# NavigationBoard.net
KiCad netlist of a schematic drawn in EAGLE
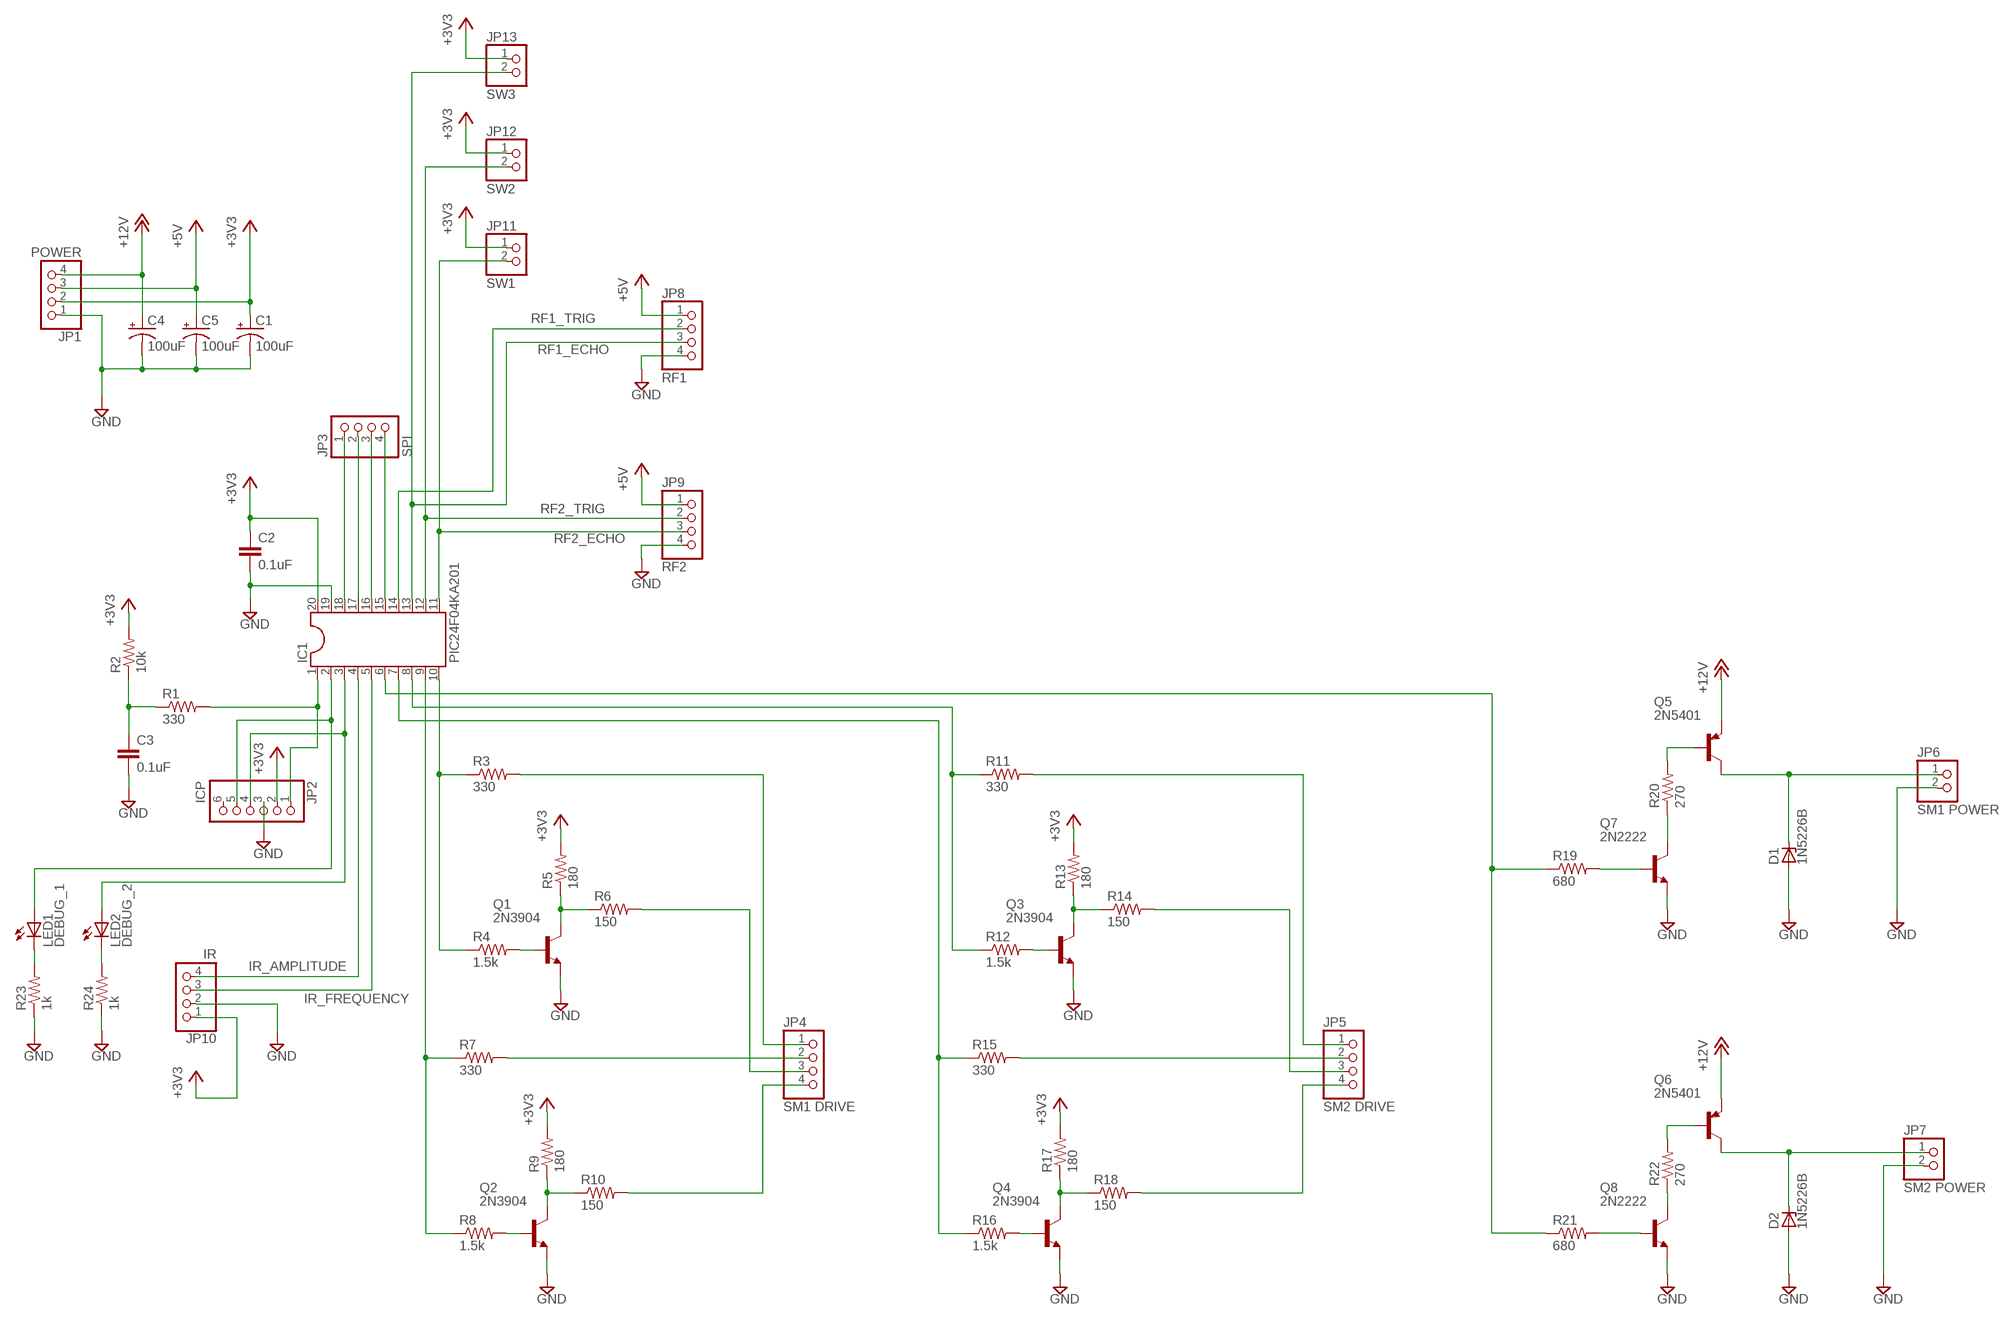
[diagram p0: schematic, sheet 1]

(export (version "E")
  (design (tool "Eeschema 10.0.6"))
  (components
    (comp (ref "C1")
      (value "100uF")
      (footprint "eagle-import:E2,5-7")
      (libsource (lib "eagle-import") (part "CPOL-USE2.5-7"))
    )
    (comp (ref "C2")
      (value "0.1uF")
      (footprint "eagle-import:C0805")
      (libsource (lib "eagle-import") (part "C-EUC0805"))
    )
    (comp (ref "C3")
      (value "0.1uF")
      (footprint "eagle-import:C0805")
      (libsource (lib "eagle-import") (part "C-EUC0805"))
    )
    (comp (ref "C4")
      (value "100uF")
      (footprint "eagle-import:E2,5-7")
      (libsource (lib "eagle-import") (part "CPOL-USE2.5-7"))
    )
    (comp (ref "C5")
      (value "100uF")
      (footprint "eagle-import:E2,5-7")
      (libsource (lib "eagle-import") (part "CPOL-USE2.5-7"))
    )
    (comp (ref "D1")
      (value "1N5226B")
      (footprint "eagle-import:DO35Z10")
      (libsource (lib "eagle-import") (part "ZPD"))
    )
    (comp (ref "D2")
      (value "1N5226B")
      (footprint "eagle-import:DO35Z10")
      (libsource (lib "eagle-import") (part "ZPD"))
    )
    (comp (ref "IC1")
      (value "PIC24F04KA201")
      (footprint "eagle-import:SOCKET-20")
      (libsource (lib "eagle-import") (part "DIL20S"))
    )
    (comp (ref "JP1")
      (value "POWER")
      (footprint "eagle-import:1X04")
      (libsource (lib "eagle-import") (part "PINHD-1X4"))
    )
    (comp (ref "JP2")
      (value "ICP")
      (footprint "eagle-import:1X06")
      (libsource (lib "eagle-import") (part "PINHD-1X6"))
    )
    (comp (ref "JP3")
      (value "SPI")
      (footprint "eagle-import:1X04")
      (libsource (lib "eagle-import") (part "PINHD-1X4"))
    )
    (comp (ref "JP4")
      (value "SM1 DRIVE")
      (footprint "eagle-import:1X04")
      (libsource (lib "eagle-import") (part "PINHD-1X4"))
    )
    (comp (ref "JP5")
      (value "SM2 DRIVE")
      (footprint "eagle-import:1X04")
      (libsource (lib "eagle-import") (part "PINHD-1X4"))
    )
    (comp (ref "JP6")
      (value "SM1 POWER")
      (footprint "eagle-import:1X02")
      (libsource (lib "eagle-import") (part "PINHD-1X2"))
    )
    (comp (ref "JP7")
      (value "SM2 POWER")
      (footprint "eagle-import:1X02")
      (libsource (lib "eagle-import") (part "PINHD-1X2"))
    )
    (comp (ref "JP8")
      (value "RF1")
      (footprint "eagle-import:1X04")
      (libsource (lib "eagle-import") (part "PINHD-1X4"))
    )
    (comp (ref "JP9")
      (value "RF2")
      (footprint "eagle-import:1X04")
      (libsource (lib "eagle-import") (part "PINHD-1X4"))
    )
    (comp (ref "JP10")
      (value "IR")
      (footprint "eagle-import:1X04")
      (libsource (lib "eagle-import") (part "PINHD-1X4"))
    )
    (comp (ref "JP11")
      (value "SW1")
      (footprint "eagle-import:1X02")
      (libsource (lib "eagle-import") (part "PINHD-1X2"))
    )
    (comp (ref "JP12")
      (value "SW2")
      (footprint "eagle-import:1X02")
      (libsource (lib "eagle-import") (part "PINHD-1X2"))
    )
    (comp (ref "JP13")
      (value "SW3")
      (footprint "eagle-import:1X02")
      (libsource (lib "eagle-import") (part "PINHD-1X2"))
    )
    (comp (ref "LED1")
      (value "DEBUG_1")
      (footprint "eagle-import:LED3MM")
      (libsource (lib "eagle-import") (part "LED3MM"))
    )
    (comp (ref "LED2")
      (value "DEBUG_2")
      (footprint "eagle-import:LED3MM")
      (libsource (lib "eagle-import") (part "LED3MM"))
    )
    (comp (ref "Q1")
      (value "2N3904")
      (footprint "eagle-import:TO92")
      (libsource (lib "eagle-import") (part "2N3904"))
    )
    (comp (ref "Q2")
      (value "2N3904")
      (footprint "eagle-import:TO92")
      (libsource (lib "eagle-import") (part "2N3904"))
    )
    (comp (ref "Q3")
      (value "2N3904")
      (footprint "eagle-import:TO92")
      (libsource (lib "eagle-import") (part "2N3904"))
    )
    (comp (ref "Q4")
      (value "2N3904")
      (footprint "eagle-import:TO92")
      (libsource (lib "eagle-import") (part "2N3904"))
    )
    (comp (ref "Q5")
      (value "2N5401")
      (footprint "eagle-import:TO92")
      (libsource (lib "eagle-import") (part "2N3906"))
    )
    (comp (ref "Q6")
      (value "2N5401")
      (footprint "eagle-import:TO92")
      (libsource (lib "eagle-import") (part "2N3906"))
    )
    (comp (ref "Q7")
      (value "2N2222")
      (footprint "eagle-import:TO92")
      (libsource (lib "eagle-import") (part "2N3904"))
    )
    (comp (ref "Q8")
      (value "2N2222")
      (footprint "eagle-import:TO92")
      (libsource (lib "eagle-import") (part "2N3904"))
    )
    (comp (ref "R1")
      (value "330")
      (footprint "eagle-import:R0805")
      (libsource (lib "eagle-import") (part "R-US_R0805"))
    )
    (comp (ref "R2")
      (value "10k")
      (footprint "eagle-import:R0805")
      (libsource (lib "eagle-import") (part "R-US_R0805"))
    )
    (comp (ref "R3")
      (value "330")
      (footprint "eagle-import:R0805")
      (libsource (lib "eagle-import") (part "R-US_R0805"))
    )
    (comp (ref "R4")
      (value "1.5k")
      (footprint "eagle-import:R0805")
      (libsource (lib "eagle-import") (part "R-US_R0805"))
    )
    (comp (ref "R5")
      (value "180")
      (footprint "eagle-import:R0805")
      (libsource (lib "eagle-import") (part "R-US_R0805"))
    )
    (comp (ref "R6")
      (value "150")
      (footprint "eagle-import:R0805")
      (libsource (lib "eagle-import") (part "R-US_R0805"))
    )
    (comp (ref "R7")
      (value "330")
      (footprint "eagle-import:R0805")
      (libsource (lib "eagle-import") (part "R-US_R0805"))
    )
    (comp (ref "R8")
      (value "1.5k")
      (footprint "eagle-import:R0805")
      (libsource (lib "eagle-import") (part "R-US_R0805"))
    )
    (comp (ref "R9")
      (value "180")
      (footprint "eagle-import:R0805")
      (libsource (lib "eagle-import") (part "R-US_R0805"))
    )
    (comp (ref "R10")
      (value "150")
      (footprint "eagle-import:R0805")
      (libsource (lib "eagle-import") (part "R-US_R0805"))
    )
    (comp (ref "R11")
      (value "330")
      (footprint "eagle-import:R0805")
      (libsource (lib "eagle-import") (part "R-US_R0805"))
    )
    (comp (ref "R12")
      (value "1.5k")
      (footprint "eagle-import:R0805")
      (libsource (lib "eagle-import") (part "R-US_R0805"))
    )
    (comp (ref "R13")
      (value "180")
      (footprint "eagle-import:R0805")
      (libsource (lib "eagle-import") (part "R-US_R0805"))
    )
    (comp (ref "R14")
      (value "150")
      (footprint "eagle-import:R0805")
      (libsource (lib "eagle-import") (part "R-US_R0805"))
    )
    (comp (ref "R15")
      (value "330")
      (footprint "eagle-import:R0805")
      (libsource (lib "eagle-import") (part "R-US_R0805"))
    )
    (comp (ref "R16")
      (value "1.5k")
      (footprint "eagle-import:R0805")
      (libsource (lib "eagle-import") (part "R-US_R0805"))
    )
    (comp (ref "R17")
      (value "180")
      (footprint "eagle-import:R0805")
      (libsource (lib "eagle-import") (part "R-US_R0805"))
    )
    (comp (ref "R18")
      (value "150")
      (footprint "eagle-import:R0805")
      (libsource (lib "eagle-import") (part "R-US_R0805"))
    )
    (comp (ref "R19")
      (value "680")
      (footprint "eagle-import:R0805")
      (libsource (lib "eagle-import") (part "R-US_R0805"))
    )
    (comp (ref "R20")
      (value "270")
      (footprint "eagle-import:R0805")
      (libsource (lib "eagle-import") (part "R-US_R0805"))
    )
    (comp (ref "R21")
      (value "680")
      (footprint "eagle-import:R0805")
      (libsource (lib "eagle-import") (part "R-US_R0805"))
    )
    (comp (ref "R22")
      (value "270")
      (footprint "eagle-import:R0805")
      (libsource (lib "eagle-import") (part "R-US_R0805"))
    )
    (comp (ref "R23")
      (value "1k")
      (footprint "eagle-import:R0805")
      (libsource (lib "eagle-import") (part "R-US_R0805"))
    )
    (comp (ref "R24")
      (value "1k")
      (footprint "eagle-import:R0805")
      (libsource (lib "eagle-import") (part "R-US_R0805"))
    )
  )
  (nets
    (net (code "1") (name "+3V3") (class "Default")
      (node (ref "C1") (pin "+") (pinfunction "+_+") (pintype "passive"))
      (node (ref "C2") (pin "1") (pinfunction "1_1") (pintype "passive"))
      (node (ref "IC1") (pin "20") (pinfunction "20_20") (pintype "passive"))
      (node (ref "JP1") (pin "2") (pinfunction "2_2") (pintype "passive"))
      (node (ref "JP10") (pin "1") (pinfunction "1_1") (pintype "passive"))
      (node (ref "JP11") (pin "1") (pinfunction "1_1") (pintype "passive"))
      (node (ref "JP12") (pin "1") (pinfunction "1_1") (pintype "passive"))
      (node (ref "JP13") (pin "1") (pinfunction "1_1") (pintype "passive"))
      (node (ref "JP2") (pin "2") (pinfunction "2_2") (pintype "passive"))
      (node (ref "R13") (pin "2") (pinfunction "2_2") (pintype "passive"))
      (node (ref "R17") (pin "2") (pinfunction "2_2") (pintype "passive"))
      (node (ref "R2") (pin "2") (pinfunction "2_2") (pintype "passive"))
      (node (ref "R5") (pin "2") (pinfunction "2_2") (pintype "passive"))
      (node (ref "R9") (pin "2") (pinfunction "2_2") (pintype "passive"))
    )
    (net (code "2") (name "+5V") (class "Default")
      (node (ref "C5") (pin "+") (pinfunction "+_+") (pintype "passive"))
      (node (ref "JP1") (pin "3") (pinfunction "3_3") (pintype "passive"))
      (node (ref "JP8") (pin "1") (pinfunction "1_1") (pintype "passive"))
      (node (ref "JP9") (pin "1") (pinfunction "1_1") (pintype "passive"))
    )
    (net (code "3") (name "+12V") (class "Default")
      (node (ref "C4") (pin "+") (pinfunction "+_+") (pintype "passive"))
      (node (ref "JP1") (pin "4") (pinfunction "4_4") (pintype "passive"))
      (node (ref "Q5") (pin "3") (pinfunction "E_3") (pintype "passive"))
      (node (ref "Q6") (pin "3") (pinfunction "E_3") (pintype "passive"))
    )
    (net (code "4") (name "/IR_AMPLITUDE") (class "Default")
      (node (ref "IC1") (pin "4") (pinfunction "4_4") (pintype "passive"))
      (node (ref "JP10") (pin "4") (pinfunction "4_4") (pintype "passive"))
    )
    (net (code "5") (name "/IR_FREQUENCY") (class "Default")
      (node (ref "IC1") (pin "5") (pinfunction "5_5") (pintype "passive"))
      (node (ref "JP10") (pin "3") (pinfunction "3_3") (pintype "passive"))
    )
    (net (code "6") (name "/RF1_ECHO") (class "Default")
      (node (ref "IC1") (pin "13") (pinfunction "13_13") (pintype "passive"))
      (node (ref "JP13") (pin "2") (pinfunction "2_2") (pintype "passive"))
      (node (ref "JP8") (pin "3") (pinfunction "3_3") (pintype "passive"))
    )
    (net (code "7") (name "/RF1_TRIG") (class "Default")
      (node (ref "IC1") (pin "14") (pinfunction "14_14") (pintype "passive"))
      (node (ref "JP8") (pin "2") (pinfunction "2_2") (pintype "passive"))
    )
    (net (code "8") (name "/RF2_ECHO") (class "Default")
      (node (ref "IC1") (pin "11") (pinfunction "11_11") (pintype "passive"))
      (node (ref "JP11") (pin "2") (pinfunction "2_2") (pintype "passive"))
      (node (ref "JP9") (pin "3") (pinfunction "3_3") (pintype "passive"))
    )
    (net (code "9") (name "/RF2_TRIG") (class "Default")
      (node (ref "IC1") (pin "12") (pinfunction "12_12") (pintype "passive"))
      (node (ref "JP12") (pin "2") (pinfunction "2_2") (pintype "passive"))
      (node (ref "JP9") (pin "2") (pinfunction "2_2") (pintype "passive"))
    )
    (net (code "10") (name "GND") (class "Default")
      (node (ref "C1") (pin "-") (pinfunction "-_-") (pintype "passive"))
      (node (ref "C2") (pin "2") (pinfunction "2_2") (pintype "passive"))
      (node (ref "C3") (pin "2") (pinfunction "2_2") (pintype "passive"))
      (node (ref "C4") (pin "-") (pinfunction "-_-") (pintype "passive"))
      (node (ref "C5") (pin "-") (pinfunction "-_-") (pintype "passive"))
      (node (ref "D1") (pin "A") (pinfunction "A_A") (pintype "passive"))
      (node (ref "D2") (pin "A") (pinfunction "A_A") (pintype "passive"))
      (node (ref "IC1") (pin "19") (pinfunction "19_19") (pintype "passive"))
      (node (ref "JP1") (pin "1") (pinfunction "1_1") (pintype "passive"))
      (node (ref "JP10") (pin "2") (pinfunction "2_2") (pintype "passive"))
      (node (ref "JP2") (pin "3") (pinfunction "3_3") (pintype "passive"))
      (node (ref "JP6") (pin "2") (pinfunction "2_2") (pintype "passive"))
      (node (ref "JP7") (pin "2") (pinfunction "2_2") (pintype "passive"))
      (node (ref "JP8") (pin "4") (pinfunction "4_4") (pintype "passive"))
      (node (ref "JP9") (pin "4") (pinfunction "4_4") (pintype "passive"))
      (node (ref "Q1") (pin "3") (pinfunction "E_3") (pintype "passive"))
      (node (ref "Q2") (pin "3") (pinfunction "E_3") (pintype "passive"))
      (node (ref "Q3") (pin "3") (pinfunction "E_3") (pintype "passive"))
      (node (ref "Q4") (pin "3") (pinfunction "E_3") (pintype "passive"))
      (node (ref "Q7") (pin "3") (pinfunction "E_3") (pintype "passive"))
      (node (ref "Q8") (pin "3") (pinfunction "E_3") (pintype "passive"))
      (node (ref "R23") (pin "1") (pinfunction "1_1") (pintype "passive"))
      (node (ref "R24") (pin "1") (pinfunction "1_1") (pintype "passive"))
    )
    (net (code "11") (name "Net-(C3-Pad1)") (class "Default")
      (node (ref "C3") (pin "1") (pinfunction "1_1") (pintype "passive"))
      (node (ref "R1") (pin "1") (pinfunction "1_1") (pintype "passive"))
      (node (ref "R2") (pin "1") (pinfunction "1_1") (pintype "passive"))
    )
    (net (code "12") (name "Net-(IC1-Pad1)") (class "Default")
      (node (ref "IC1") (pin "1") (pinfunction "1_1") (pintype "passive"))
      (node (ref "JP2") (pin "1") (pinfunction "1_1") (pintype "passive"))
      (node (ref "R1") (pin "2") (pinfunction "2_2") (pintype "passive"))
    )
    (net (code "13") (name "Net-(IC1-Pad2)") (class "Default")
      (node (ref "IC1") (pin "2") (pinfunction "2_2") (pintype "passive"))
      (node (ref "JP2") (pin "5") (pinfunction "5_5") (pintype "passive"))
      (node (ref "LED1") (pin "A") (pinfunction "A_A") (pintype "passive"))
    )
    (net (code "14") (name "Net-(IC1-Pad3)") (class "Default")
      (node (ref "IC1") (pin "3") (pinfunction "3_3") (pintype "passive"))
      (node (ref "JP2") (pin "4") (pinfunction "4_4") (pintype "passive"))
      (node (ref "LED2") (pin "A") (pinfunction "A_A") (pintype "passive"))
    )
    (net (code "15") (name "Net-(IC1-Pad6)") (class "Default")
      (node (ref "IC1") (pin "6") (pinfunction "6_6") (pintype "passive"))
      (node (ref "R19") (pin "1") (pinfunction "1_1") (pintype "passive"))
      (node (ref "R21") (pin "1") (pinfunction "1_1") (pintype "passive"))
    )
    (net (code "16") (name "Net-(IC1-Pad7)") (class "Default")
      (node (ref "IC1") (pin "7") (pinfunction "7_7") (pintype "passive"))
      (node (ref "R15") (pin "1") (pinfunction "1_1") (pintype "passive"))
      (node (ref "R16") (pin "1") (pinfunction "1_1") (pintype "passive"))
    )
    (net (code "17") (name "Net-(IC1-Pad8)") (class "Default")
      (node (ref "IC1") (pin "8") (pinfunction "8_8") (pintype "passive"))
      (node (ref "R11") (pin "1") (pinfunction "1_1") (pintype "passive"))
      (node (ref "R12") (pin "1") (pinfunction "1_1") (pintype "passive"))
    )
    (net (code "18") (name "Net-(IC1-Pad9)") (class "Default")
      (node (ref "IC1") (pin "9") (pinfunction "9_9") (pintype "passive"))
      (node (ref "R7") (pin "1") (pinfunction "1_1") (pintype "passive"))
      (node (ref "R8") (pin "1") (pinfunction "1_1") (pintype "passive"))
    )
    (net (code "19") (name "Net-(IC1-Pad10)") (class "Default")
      (node (ref "IC1") (pin "10") (pinfunction "10_10") (pintype "passive"))
      (node (ref "R3") (pin "1") (pinfunction "1_1") (pintype "passive"))
      (node (ref "R4") (pin "1") (pinfunction "1_1") (pintype "passive"))
    )
    (net (code "20") (name "Net-(IC1-Pad15)") (class "Default")
      (node (ref "IC1") (pin "15") (pinfunction "15_15") (pintype "passive"))
      (node (ref "JP3") (pin "4") (pinfunction "4_4") (pintype "passive"))
    )
    (net (code "21") (name "Net-(IC1-Pad16)") (class "Default")
      (node (ref "IC1") (pin "16") (pinfunction "16_16") (pintype "passive"))
      (node (ref "JP3") (pin "3") (pinfunction "3_3") (pintype "passive"))
    )
    (net (code "22") (name "Net-(IC1-Pad17)") (class "Default")
      (node (ref "IC1") (pin "17") (pinfunction "17_17") (pintype "passive"))
      (node (ref "JP3") (pin "2") (pinfunction "2_2") (pintype "passive"))
    )
    (net (code "23") (name "Net-(IC1-Pad18)") (class "Default")
      (node (ref "IC1") (pin "18") (pinfunction "18_18") (pintype "passive"))
      (node (ref "JP3") (pin "1") (pinfunction "1_1") (pintype "passive"))
    )
    (net (code "24") (name "Net-(JP4-Pad1)") (class "Default")
      (node (ref "JP4") (pin "1") (pinfunction "1_1") (pintype "passive"))
      (node (ref "R3") (pin "2") (pinfunction "2_2") (pintype "passive"))
    )
    (net (code "25") (name "Net-(JP4-Pad2)") (class "Default")
      (node (ref "JP4") (pin "2") (pinfunction "2_2") (pintype "passive"))
      (node (ref "R7") (pin "2") (pinfunction "2_2") (pintype "passive"))
    )
    (net (code "26") (name "Net-(JP4-Pad3)") (class "Default")
      (node (ref "JP4") (pin "3") (pinfunction "3_3") (pintype "passive"))
      (node (ref "R6") (pin "2") (pinfunction "2_2") (pintype "passive"))
    )
    (net (code "27") (name "Net-(JP4-Pad4)") (class "Default")
      (node (ref "JP4") (pin "4") (pinfunction "4_4") (pintype "passive"))
      (node (ref "R10") (pin "2") (pinfunction "2_2") (pintype "passive"))
    )
    (net (code "28") (name "Net-(JP5-Pad1)") (class "Default")
      (node (ref "JP5") (pin "1") (pinfunction "1_1") (pintype "passive"))
      (node (ref "R11") (pin "2") (pinfunction "2_2") (pintype "passive"))
    )
    (net (code "29") (name "Net-(JP5-Pad2)") (class "Default")
      (node (ref "JP5") (pin "2") (pinfunction "2_2") (pintype "passive"))
      (node (ref "R15") (pin "2") (pinfunction "2_2") (pintype "passive"))
    )
    (net (code "30") (name "Net-(JP5-Pad3)") (class "Default")
      (node (ref "JP5") (pin "3") (pinfunction "3_3") (pintype "passive"))
      (node (ref "R14") (pin "2") (pinfunction "2_2") (pintype "passive"))
    )
    (net (code "31") (name "Net-(JP5-Pad4)") (class "Default")
      (node (ref "JP5") (pin "4") (pinfunction "4_4") (pintype "passive"))
      (node (ref "R18") (pin "2") (pinfunction "2_2") (pintype "passive"))
    )
    (net (code "32") (name "Net-(LED1-C)") (class "Default")
      (node (ref "LED1") (pin "K") (pinfunction "C_K") (pintype "passive"))
      (node (ref "R23") (pin "2") (pinfunction "2_2") (pintype "passive"))
    )
    (net (code "33") (name "Net-(LED2-C)") (class "Default")
      (node (ref "LED2") (pin "K") (pinfunction "C_K") (pintype "passive"))
      (node (ref "R24") (pin "2") (pinfunction "2_2") (pintype "passive"))
    )
    (net (code "34") (name "Net-(Q1-B)") (class "Default")
      (node (ref "Q1") (pin "2") (pinfunction "B_2") (pintype "passive"))
      (node (ref "R4") (pin "2") (pinfunction "2_2") (pintype "passive"))
    )
    (net (code "35") (name "Net-(Q1-C)") (class "Default")
      (node (ref "Q1") (pin "1") (pinfunction "C_1") (pintype "passive"))
      (node (ref "R5") (pin "1") (pinfunction "1_1") (pintype "passive"))
      (node (ref "R6") (pin "1") (pinfunction "1_1") (pintype "passive"))
    )
    (net (code "36") (name "Net-(Q2-B)") (class "Default")
      (node (ref "Q2") (pin "2") (pinfunction "B_2") (pintype "passive"))
      (node (ref "R8") (pin "2") (pinfunction "2_2") (pintype "passive"))
    )
    (net (code "37") (name "Net-(Q2-C)") (class "Default")
      (node (ref "Q2") (pin "1") (pinfunction "C_1") (pintype "passive"))
      (node (ref "R10") (pin "1") (pinfunction "1_1") (pintype "passive"))
      (node (ref "R9") (pin "1") (pinfunction "1_1") (pintype "passive"))
    )
    (net (code "38") (name "Net-(Q3-B)") (class "Default")
      (node (ref "Q3") (pin "2") (pinfunction "B_2") (pintype "passive"))
      (node (ref "R12") (pin "2") (pinfunction "2_2") (pintype "passive"))
    )
    (net (code "39") (name "Net-(Q3-C)") (class "Default")
      (node (ref "Q3") (pin "1") (pinfunction "C_1") (pintype "passive"))
      (node (ref "R13") (pin "1") (pinfunction "1_1") (pintype "passive"))
      (node (ref "R14") (pin "1") (pinfunction "1_1") (pintype "passive"))
    )
    (net (code "40") (name "Net-(Q4-B)") (class "Default")
      (node (ref "Q4") (pin "2") (pinfunction "B_2") (pintype "passive"))
      (node (ref "R16") (pin "2") (pinfunction "2_2") (pintype "passive"))
    )
    (net (code "41") (name "Net-(Q4-C)") (class "Default")
      (node (ref "Q4") (pin "1") (pinfunction "C_1") (pintype "passive"))
      (node (ref "R17") (pin "1") (pinfunction "1_1") (pintype "passive"))
      (node (ref "R18") (pin "1") (pinfunction "1_1") (pintype "passive"))
    )
    (net (code "42") (name "Net-(Q5-B)") (class "Default")
      (node (ref "Q5") (pin "2") (pinfunction "B_2") (pintype "passive"))
      (node (ref "R20") (pin "2") (pinfunction "2_2") (pintype "passive"))
    )
    (net (code "43") (name "Net-(Q5-C)") (class "Default")
      (node (ref "D1") (pin "C") (pinfunction "C_C") (pintype "passive"))
      (node (ref "JP6") (pin "1") (pinfunction "1_1") (pintype "passive"))
      (node (ref "Q5") (pin "1") (pinfunction "C_1") (pintype "passive"))
    )
    (net (code "44") (name "Net-(Q6-B)") (class "Default")
      (node (ref "Q6") (pin "2") (pinfunction "B_2") (pintype "passive"))
      (node (ref "R22") (pin "2") (pinfunction "2_2") (pintype "passive"))
    )
    (net (code "45") (name "Net-(Q6-C)") (class "Default")
      (node (ref "D2") (pin "C") (pinfunction "C_C") (pintype "passive"))
      (node (ref "JP7") (pin "1") (pinfunction "1_1") (pintype "passive"))
      (node (ref "Q6") (pin "1") (pinfunction "C_1") (pintype "passive"))
    )
    (net (code "46") (name "Net-(Q7-B)") (class "Default")
      (node (ref "Q7") (pin "2") (pinfunction "B_2") (pintype "passive"))
      (node (ref "R19") (pin "2") (pinfunction "2_2") (pintype "passive"))
    )
    (net (code "47") (name "Net-(Q7-C)") (class "Default")
      (node (ref "Q7") (pin "1") (pinfunction "C_1") (pintype "passive"))
      (node (ref "R20") (pin "1") (pinfunction "1_1") (pintype "passive"))
    )
    (net (code "48") (name "Net-(Q8-B)") (class "Default")
      (node (ref "Q8") (pin "2") (pinfunction "B_2") (pintype "passive"))
      (node (ref "R21") (pin "2") (pinfunction "2_2") (pintype "passive"))
    )
    (net (code "49") (name "Net-(Q8-C)") (class "Default")
      (node (ref "Q8") (pin "1") (pinfunction "C_1") (pintype "passive"))
      (node (ref "R22") (pin "1") (pinfunction "1_1") (pintype "passive"))
    )
    (net (code "50") (name "unconnected-(JP2-Pad6)") (class "Default")
      (node (ref "JP2") (pin "6") (pinfunction "6_6") (pintype "passive"))
    )
  )
)
